# External_Battery.net
KiCad netlist of a schematic drawn in EAGLE
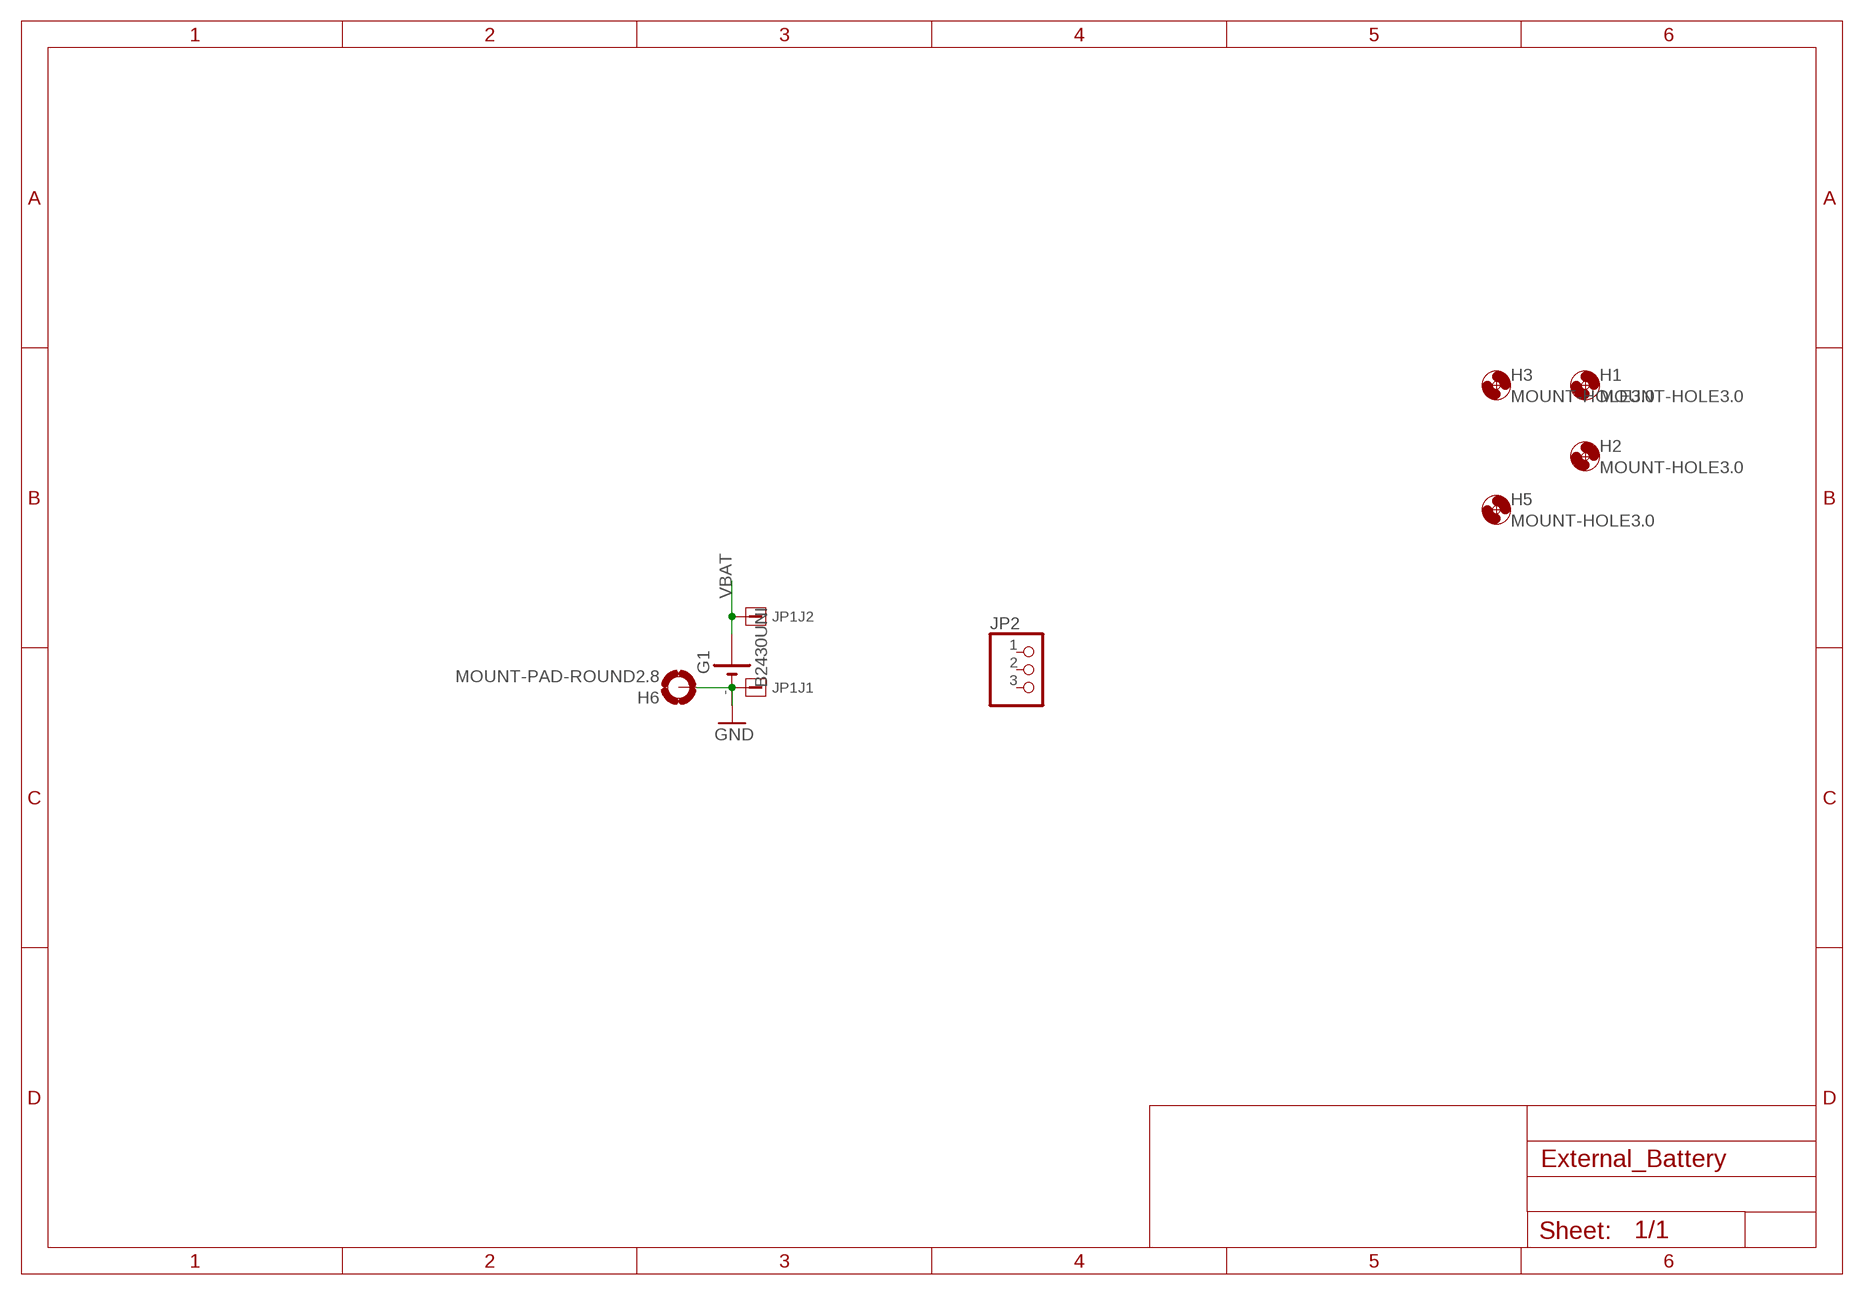
[diagram p0: schematic, sheet 1]

(export (version "E")
  (design (tool "Eeschema 10.0.6"))
  (components
    (comp (ref "G1")
      (value "B2430UNI")
      (footprint "eagle-import:B2430UNI")
      (libsource (lib "eagle-import") (part "B2430UNI"))
    )
    (comp (ref "H1")
      (value "MOUNT-HOLE3.0")
      (footprint "eagle-import:3,0")
      (libsource (lib "eagle-import") (part "MOUNT-HOLE3.0"))
    )
    (comp (ref "H2")
      (value "MOUNT-HOLE3.0")
      (footprint "eagle-import:3,0")
      (libsource (lib "eagle-import") (part "MOUNT-HOLE3.0"))
    )
    (comp (ref "H3")
      (value "MOUNT-HOLE3.0")
      (footprint "eagle-import:3,0")
      (libsource (lib "eagle-import") (part "MOUNT-HOLE3.0"))
    )
    (comp (ref "H5")
      (value "MOUNT-HOLE3.0")
      (footprint "eagle-import:3,0")
      (libsource (lib "eagle-import") (part "MOUNT-HOLE3.0"))
    )
    (comp (ref "H6")
      (value "MOUNT-PAD-ROUND2.8")
      (footprint "eagle-import:2,8-PAD")
      (libsource (lib "eagle-import") (part "MOUNT-PAD-ROUND2.8"))
    )
    (comp (ref "JP1")
      (value "CON2-3.81")
      (footprint "eagle-import:CON2-3.81")
      (libsource (lib "eagle-import") (part "CON2-3.81"))
    )
    (comp (ref "JP2")
      (value "PINHD-1X3")
      (footprint "eagle-import:1X03")
      (libsource (lib "eagle-import") (part "PINHD-1X3"))
    )
  )
  (nets
    (net (code "1") (name "/VBAT") (class "Default")
      (node (ref "G1") (pin "+@4") (pinfunction "+_+@4") (pintype "passive"))
      (node (ref "JP1") (pin "2") (pinfunction "1_2") (pintype "passive"))
    )
    (net (code "2") (name "GND") (class "Default")
      (node (ref "G1") (pin "-") (pinfunction "-_-") (pintype "passive"))
      (node (ref "G1") (pin "-@1") (pinfunction "-_-@1") (pintype "passive"))
      (node (ref "H6") (pin "B2,8") (pinfunction "MOUNT_B2,8") (pintype "passive"))
      (node (ref "JP1") (pin "1") (pinfunction "1_1") (pintype "passive"))
    )
    (net (code "3") (name "unconnected-(JP2-Pad1)") (class "Default")
      (node (ref "JP2") (pin "1") (pinfunction "1_1") (pintype "passive"))
    )
    (net (code "4") (name "unconnected-(JP2-Pad2)") (class "Default")
      (node (ref "JP2") (pin "2") (pinfunction "2_2") (pintype "passive"))
    )
    (net (code "5") (name "unconnected-(JP2-Pad3)") (class "Default")
      (node (ref "JP2") (pin "3") (pinfunction "3_3") (pintype "passive"))
    )
  )
)
